# Sheet1.net
KiCad netlist of a schematic drawn in Altium Designer
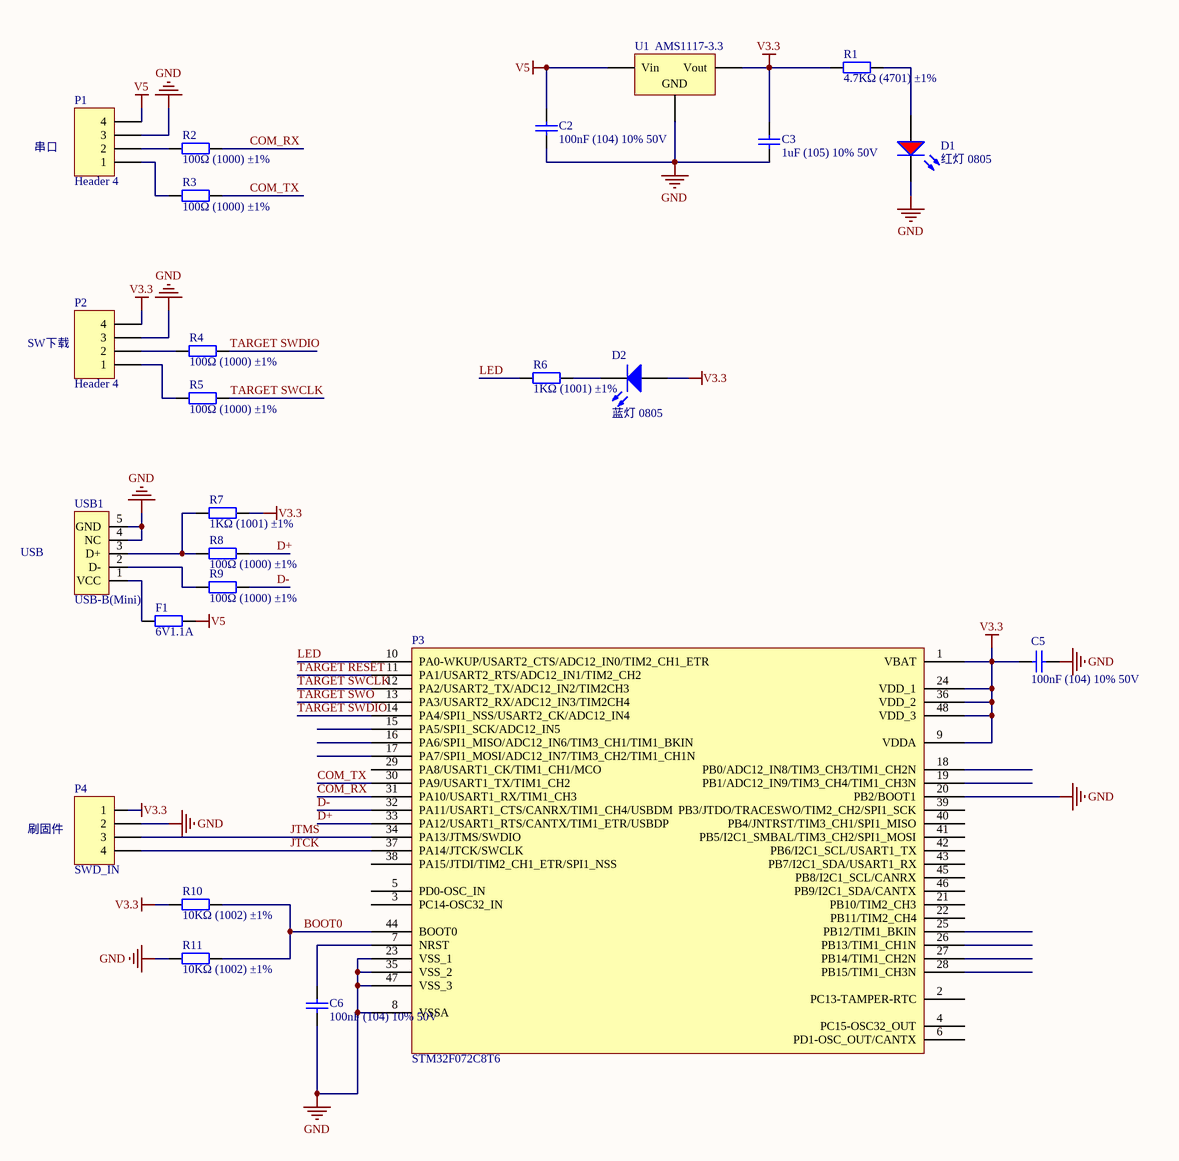
[diagram p0: Sheet1.SchDoc]

(export (version "E")
  (design (tool "Eeschema 10.0.6"))
  (components
    (comp (ref "C2")
      (value "100nF (104) 10% 50V")
      (footprint "0603_C")
      (description "贴片电容")
      (libsource (lib "Miscellaneous Devices LC") (part "0603 100nF (104) 10% 50V"))
    )
    (comp (ref "C3")
      (value "1uF (105) 10% 50V")
      (footprint "0603_C")
      (description "贴片电容")
      (libsource (lib "Miscellaneous Devices LC") (part "0603 1uF (105) 10% 50V"))
    )
    (comp (ref "C5")
      (value "100nF (104) 10% 50V")
      (footprint "0603_C")
      (description "贴片电容")
      (libsource (lib "Miscellaneous Devices LC") (part "0603 100nF (104) 10% 50V"))
    )
    (comp (ref "C6")
      (value "100nF (104) 10% 50V")
      (footprint "0603_C")
      (description "贴片电容")
      (libsource (lib "Miscellaneous Devices LC") (part "0603 100nF (104) 10% 50V"))
    )
    (comp (ref "D1")
      (value "红灯 0805")
      (footprint "0805_LED_S1")
      (description "发光二极管")
      (libsource (lib "Miscellaneous Devices LC") (part "0805 红灯"))
    )
    (comp (ref "D2")
      (value "蓝灯 0805")
      (footprint "0805_LED_S1")
      (description "发光二极管")
      (libsource (lib "Miscellaneous Devices LC") (part "0805 蓝灯"))
    )
    (comp (ref "F1")
      (value "6V1.1A")
      (footprint "0603_R")
      (description "贴片电阻")
      (libsource (lib "Miscellaneous Devices LC") (part "0603 0Ω (0R0) 1%"))
    )
    (comp (ref "P1")
      (value "Header 4")
      (footprint "IDE4_D")
      (description "Header, 4-Pin")
      (fields (field (name "PUBLISHER") "Altium Limited"))
      (libsource (lib "Miscellaneous Connectors") (part "Header 4"))
    )
    (comp (ref "P2")
      (value "Header 4")
      (footprint "IDE4_D")
      (description "Header, 4-Pin")
      (fields (field (name "PUBLISHER") "Altium Limited"))
      (libsource (lib "Miscellaneous Connectors") (part "Header 4"))
    )
    (comp (ref "P3")
      (value "STM32F072C8T6")
      (footprint "LQFP48_7X7X05P")
      (libsource (lib "MY_倒车雷达") (part "stm32f103v8t6"))
    )
    (comp (ref "P4")
      (value "SWD_IN")
      (footprint "HDR1X4")
      (description "Header, 4-Pin")
      (fields (field (name "PUBLISHER") "Altium Limited"))
      (libsource (lib "") (part "Header 4_1"))
    )
    (comp (ref "R1")
      (value "4.7KΩ (4701) ±1%")
      (footprint "0603_R")
      (description "贴片电阻")
      (libsource (lib "Miscellaneous Devices LC") (part "0603 4.7KΩ (4701) 1%"))
    )
    (comp (ref "R2")
      (value "100Ω (1000) ±1%")
      (footprint "0603_R")
      (description "贴片电阻")
      (libsource (lib "Miscellaneous Devices LC") (part "0603 100Ω (1000) 1%"))
    )
    (comp (ref "R3")
      (value "100Ω (1000) ±1%")
      (footprint "0603_R")
      (description "贴片电阻")
      (libsource (lib "Miscellaneous Devices LC") (part "0603 100Ω (1000) 1%"))
    )
    (comp (ref "R4")
      (value "100Ω (1000) ±1%")
      (footprint "0603_R")
      (description "贴片电阻")
      (libsource (lib "Miscellaneous Devices LC") (part "0603 100Ω (1000) 1%"))
    )
    (comp (ref "R5")
      (value "100Ω (1000) ±1%")
      (footprint "0603_R")
      (description "贴片电阻")
      (libsource (lib "Miscellaneous Devices LC") (part "0603 100Ω (1000) 1%"))
    )
    (comp (ref "R6")
      (value "1KΩ (1001) ±1%")
      (footprint "0603_R")
      (description "贴片电阻")
      (libsource (lib "Miscellaneous Devices LC") (part "0603 1KΩ (1001) 1%"))
    )
    (comp (ref "R7")
      (value "1KΩ (1001) ±1%")
      (footprint "0603_R")
      (description "贴片电阻")
      (libsource (lib "Miscellaneous Devices LC") (part "0603 1KΩ (1001) 1%"))
    )
    (comp (ref "R8")
      (value "100Ω (1000) ±1%")
      (footprint "0603_R")
      (description "贴片电阻")
      (libsource (lib "Miscellaneous Devices LC") (part "0603 100Ω (1000) 1%"))
    )
    (comp (ref "R9")
      (value "100Ω (1000) ±1%")
      (footprint "0603_R")
      (description "贴片电阻")
      (libsource (lib "Miscellaneous Devices LC") (part "0603 100Ω (1000) 1%"))
    )
    (comp (ref "R10")
      (value "10KΩ (1002) ±1%")
      (footprint "0603_R")
      (description "贴片电阻")
      (libsource (lib "Miscellaneous Devices LC") (part "0603 10KΩ (1002) 1%"))
    )
    (comp (ref "R11")
      (value "10KΩ (1002) ±1%")
      (footprint "0603_R")
      (description "贴片电阻")
      (libsource (lib "Miscellaneous Devices LC") (part "0603 10KΩ (1002) 1%"))
    )
    (comp (ref "U1")
      (value "AMS1117-3.3")
      (footprint "SOT-223")
      (description "低压差线性稳压(LDO)")
      (libsource (lib "Miscellaneous Devices LC") (part "SOT-223 AMS1117-3.3"))
    )
    (comp (ref "USB1")
      (value "USB-B(Mini)")
      (footprint "miniUSB")
      (libsource (lib "MY_倒车雷达") (part "miniUSB"))
    )
  )
  (nets
    (net (code "1") (name "/BOOT0") (class "Default")
      (node (ref "P3") (pin "44") (pinfunction "BOOT0_44") (pintype "passive"))
      (node (ref "R10") (pin "2") (pinfunction "2_2") (pintype "passive"))
      (node (ref "R11") (pin "2") (pinfunction "2_2") (pintype "passive"))
    )
    (net (code "2") (name "/COM_RX") (class "Default")
      (node (ref "P3") (pin "31") (pinfunction "PA10/USART1_RX/TIM1_CH3_31") (pintype "passive"))
      (node (ref "R2") (pin "2") (pinfunction "2_2") (pintype "passive"))
    )
    (net (code "3") (name "/COM_TX") (class "Default")
      (node (ref "P3") (pin "30") (pinfunction "PA9/USART1_TX/TIM1_CH2_30") (pintype "passive"))
      (node (ref "R3") (pin "2") (pinfunction "2_2") (pintype "passive"))
    )
    (net (code "4") (name "/D+") (class "Default")
      (node (ref "P3") (pin "33") (pinfunction "PA12/USART1_RTS/CANTX/TIM1_ETR/USBDP_33") (pintype "passive"))
      (node (ref "R8") (pin "2") (pinfunction "2_2") (pintype "passive"))
    )
    (net (code "5") (name "/D-") (class "Default")
      (node (ref "P3") (pin "32") (pinfunction "PA11/USART1_CTS/CANRX/TIM1_CH4/USBDM_32") (pintype "passive"))
      (node (ref "R9") (pin "2") (pinfunction "2_2") (pintype "passive"))
    )
    (net (code "6") (name "/JTCK") (class "Default")
      (node (ref "P3") (pin "37") (pinfunction "PA14/JTCK/SWCLK_37") (pintype "passive"))
      (node (ref "P4") (pin "4") (pinfunction "4_4") (pintype "passive"))
    )
    (net (code "7") (name "/JTMS") (class "Default")
      (node (ref "P3") (pin "34") (pinfunction "PA13/JTMS/SWDIO_34") (pintype "passive"))
      (node (ref "P4") (pin "3") (pinfunction "3_3") (pintype "passive"))
    )
    (net (code "8") (name "/LED") (class "Default")
      (node (ref "P3") (pin "10") (pinfunction "PA0-WKUP/USART2_CTS/ADC12_IN0/TIM2_CH1_ETR_10") (pintype "passive"))
      (node (ref "R6") (pin "1") (pinfunction "1_1") (pintype "passive"))
    )
    (net (code "9") (name "/TARGET RESET") (class "Default")
      (node (ref "P3") (pin "11") (pinfunction "PA1/USART2_RTS/ADC12_IN1/TIM2_CH2_11") (pintype "passive"))
    )
    (net (code "10") (name "/TARGET SWCLK") (class "Default")
      (node (ref "P3") (pin "12") (pinfunction "PA2/USART2_TX/ADC12_IN2/TIM2CH3_12") (pintype "passive"))
      (node (ref "R5") (pin "2") (pinfunction "2_2") (pintype "passive"))
    )
    (net (code "11") (name "/TARGET SWDIO") (class "Default")
      (node (ref "P3") (pin "14") (pinfunction "PA4/SPI1_NSS/USART2_CK/ADC12_IN4_14") (pintype "passive"))
      (node (ref "R4") (pin "2") (pinfunction "2_2") (pintype "passive"))
    )
    (net (code "12") (name "/TARGET SWO") (class "Default")
      (node (ref "P3") (pin "13") (pinfunction "PA3/USART2_RX/ADC12_IN3/TIM2CH4_13") (pintype "passive"))
    )
    (net (code "13") (name "GND") (class "Default")
      (node (ref "C2") (pin "2") (pinfunction "2_2") (pintype "passive"))
      (node (ref "C3") (pin "2") (pinfunction "2_2") (pintype "passive"))
      (node (ref "C5") (pin "2") (pinfunction "2_2") (pintype "passive"))
      (node (ref "C6") (pin "2") (pinfunction "2_2") (pintype "passive"))
      (node (ref "D1") (pin "K") (pinfunction "K_K") (pintype "passive"))
      (node (ref "P1") (pin "3") (pinfunction "3_3") (pintype "passive"))
      (node (ref "P2") (pin "3") (pinfunction "3_3") (pintype "passive"))
      (node (ref "P3") (pin "20") (pinfunction "PB2/BOOT1_20") (pintype "passive"))
      (node (ref "P3") (pin "23") (pinfunction "VSS_1_23") (pintype "passive"))
      (node (ref "P3") (pin "35") (pinfunction "VSS_2_35") (pintype "passive"))
      (node (ref "P3") (pin "47") (pinfunction "VSS_3_47") (pintype "passive"))
      (node (ref "P3") (pin "8") (pinfunction "VSSA_8") (pintype "passive"))
      (node (ref "P4") (pin "2") (pinfunction "2_2") (pintype "passive"))
      (node (ref "R11") (pin "1") (pinfunction "1_1") (pintype "passive"))
      (node (ref "U1") (pin "1") (pinfunction "GND_1") (pintype "passive"))
      (node (ref "USB1") (pin "4") (pinfunction "NC_4") (pintype "passive"))
      (node (ref "USB1") (pin "5") (pinfunction "GND_5") (pintype "passive"))
    )
    (net (code "14") (name "Net-(D1-PadA)") (class "Default")
      (node (ref "D1") (pin "A") (pinfunction "A_A") (pintype "passive"))
      (node (ref "R1") (pin "2") (pinfunction "2_2") (pintype "passive"))
    )
    (net (code "15") (name "Net-(D2-PadK)") (class "Default")
      (node (ref "D2") (pin "K") (pinfunction "K_K") (pintype "passive"))
      (node (ref "R6") (pin "2") (pinfunction "2_2") (pintype "passive"))
    )
    (net (code "16") (name "Net-(P1-Pad1)") (class "Default")
      (node (ref "P1") (pin "1") (pinfunction "1_1") (pintype "passive"))
      (node (ref "R3") (pin "1") (pinfunction "1_1") (pintype "passive"))
    )
    (net (code "17") (name "Net-(P1-Pad2)") (class "Default")
      (node (ref "P1") (pin "2") (pinfunction "2_2") (pintype "passive"))
      (node (ref "R2") (pin "1") (pinfunction "1_1") (pintype "passive"))
    )
    (net (code "18") (name "Net-(P2-Pad1)") (class "Default")
      (node (ref "P2") (pin "1") (pinfunction "1_1") (pintype "passive"))
      (node (ref "R5") (pin "1") (pinfunction "1_1") (pintype "passive"))
    )
    (net (code "19") (name "Net-(P2-Pad2)") (class "Default")
      (node (ref "P2") (pin "2") (pinfunction "2_2") (pintype "passive"))
      (node (ref "R4") (pin "1") (pinfunction "1_1") (pintype "passive"))
    )
    (net (code "20") (name "Net-(P3-NRST)") (class "Default")
      (node (ref "C6") (pin "1") (pinfunction "1_1") (pintype "passive"))
      (node (ref "P3") (pin "7") (pinfunction "NRST_7") (pintype "passive"))
    )
    (net (code "21") (name "Net-(USB1-D+)") (class "Default")
      (node (ref "R7") (pin "1") (pinfunction "1_1") (pintype "passive"))
      (node (ref "R8") (pin "1") (pinfunction "1_1") (pintype "passive"))
      (node (ref "USB1") (pin "3") (pinfunction "D+_3") (pintype "passive"))
    )
    (net (code "22") (name "Net-(USB1-D-)") (class "Default")
      (node (ref "R9") (pin "1") (pinfunction "1_1") (pintype "passive"))
      (node (ref "USB1") (pin "2") (pinfunction "D-_2") (pintype "passive"))
    )
    (net (code "23") (name "Net-(USB1-VCC)") (class "Default")
      (node (ref "F1") (pin "1") (pinfunction "1_1") (pintype "passive"))
      (node (ref "USB1") (pin "1") (pinfunction "VCC_1") (pintype "passive"))
    )
    (net (code "24") (name "V3.3") (class "Default")
      (node (ref "C3") (pin "1") (pinfunction "1_1") (pintype "passive"))
      (node (ref "C5") (pin "1") (pinfunction "1_1") (pintype "passive"))
      (node (ref "D2") (pin "A") (pinfunction "A_A") (pintype "passive"))
      (node (ref "P2") (pin "4") (pinfunction "4_4") (pintype "passive"))
      (node (ref "P3") (pin "1") (pinfunction "VBAT_1") (pintype "passive"))
      (node (ref "P3") (pin "24") (pinfunction "VDD_1_24") (pintype "passive"))
      (node (ref "P3") (pin "36") (pinfunction "VDD_2_36") (pintype "passive"))
      (node (ref "P3") (pin "48") (pinfunction "VDD_3_48") (pintype "passive"))
      (node (ref "P3") (pin "9") (pinfunction "VDDA_9") (pintype "passive"))
      (node (ref "P4") (pin "1") (pinfunction "1_1") (pintype "passive"))
      (node (ref "R1") (pin "1") (pinfunction "1_1") (pintype "passive"))
      (node (ref "R10") (pin "1") (pinfunction "1_1") (pintype "passive"))
      (node (ref "R7") (pin "2") (pinfunction "2_2") (pintype "passive"))
      (node (ref "U1") (pin "2") (pinfunction "Vout_2") (pintype "passive"))
    )
    (net (code "25") (name "V5") (class "Default")
      (node (ref "C2") (pin "1") (pinfunction "1_1") (pintype "passive"))
      (node (ref "F1") (pin "2") (pinfunction "2_2") (pintype "passive"))
      (node (ref "P1") (pin "4") (pinfunction "4_4") (pintype "passive"))
      (node (ref "U1") (pin "3") (pinfunction "Vin_3") (pintype "passive"))
    )
    (net (code "26") (name "unconnected-(P3-PA5{slash}SPI1_SCK{slash}ADC12_IN5-Pad15)") (class "Default")
      (node (ref "P3") (pin "15") (pinfunction "PA5/SPI1_SCK/ADC12_IN5_15") (pintype "passive"))
    )
    (net (code "27") (name "unconnected-(P3-PA6{slash}SPI1_MISO{slash}ADC12_IN6{slash}TIM3_CH1{slash}TIM1_BKIN-Pad16)") (class "Default")
      (node (ref "P3") (pin "16") (pinfunction "PA6/SPI1_MISO/ADC12_IN6/TIM3_CH1/TIM1_BKIN_16") (pintype "passive"))
    )
    (net (code "28") (name "unconnected-(P3-PA7{slash}SPI1_MOSI{slash}ADC12_IN7{slash}TIM3_CH2{slash}TIM1_CH1N-Pad17)") (class "Default")
      (node (ref "P3") (pin "17") (pinfunction "PA7/SPI1_MOSI/ADC12_IN7/TIM3_CH2/TIM1_CH1N_17") (pintype "passive"))
    )
    (net (code "29") (name "unconnected-(P3-PA8{slash}USART1_CK{slash}TIM1_CH1{slash}MCO-Pad29)") (class "Default")
      (node (ref "P3") (pin "29") (pinfunction "PA8/USART1_CK/TIM1_CH1/MCO_29") (pintype "passive"))
    )
    (net (code "30") (name "unconnected-(P3-PA15{slash}JTDI{slash}TIM2_CH1_ETR{slash}SPI1_NSS-Pad38)") (class "Default")
      (node (ref "P3") (pin "38") (pinfunction "PA15/JTDI/TIM2_CH1_ETR/SPI1_NSS_38") (pintype "passive"))
    )
    (net (code "31") (name "unconnected-(P3-PB0{slash}ADC12_IN8{slash}TIM3_CH3{slash}TIM1_CH2N-Pad18)") (class "Default")
      (node (ref "P3") (pin "18") (pinfunction "PB0/ADC12_IN8/TIM3_CH3/TIM1_CH2N_18") (pintype "passive"))
    )
    (net (code "32") (name "unconnected-(P3-PB1{slash}ADC12_IN9{slash}TIM3_CH4{slash}TIM1_CH3N-Pad19)") (class "Default")
      (node (ref "P3") (pin "19") (pinfunction "PB1/ADC12_IN9/TIM3_CH4/TIM1_CH3N_19") (pintype "passive"))
    )
    (net (code "33") (name "unconnected-(P3-PB3{slash}JTDO{slash}TRACESWO{slash}TIM2_CH2{slash}SPI1_SCK-Pad39)") (class "Default")
      (node (ref "P3") (pin "39") (pinfunction "PB3/JTDO/TRACESWO/TIM2_CH2/SPI1_SCK_39") (pintype "passive"))
    )
    (net (code "34") (name "unconnected-(P3-PB4{slash}JNTRST{slash}TIM3_CH1{slash}SPI1_MISO-Pad40)") (class "Default")
      (node (ref "P3") (pin "40") (pinfunction "PB4/JNTRST/TIM3_CH1/SPI1_MISO_40") (pintype "passive"))
    )
    (net (code "35") (name "unconnected-(P3-PB5{slash}I2C1_SMBAL{slash}TIM3_CH2{slash}SPI1_MOSI-Pad41)") (class "Default")
      (node (ref "P3") (pin "41") (pinfunction "PB5/I2C1_SMBAL/TIM3_CH2/SPI1_MOSI_41") (pintype "passive"))
    )
    (net (code "36") (name "unconnected-(P3-PB6{slash}I2C1_SCL{slash}USART1_TX-Pad42)") (class "Default")
      (node (ref "P3") (pin "42") (pinfunction "PB6/I2C1_SCL/USART1_TX_42") (pintype "passive"))
    )
    (net (code "37") (name "unconnected-(P3-PB7{slash}I2C1_SDA{slash}USART1_RX-Pad43)") (class "Default")
      (node (ref "P3") (pin "43") (pinfunction "PB7/I2C1_SDA/USART1_RX_43") (pintype "passive"))
    )
    (net (code "38") (name "unconnected-(P3-PB8{slash}I2C1_SCL{slash}CANRX-Pad45)") (class "Default")
      (node (ref "P3") (pin "45") (pinfunction "PB8/I2C1_SCL/CANRX_45") (pintype "passive"))
    )
    (net (code "39") (name "unconnected-(P3-PB9{slash}I2C1_SDA{slash}CANTX-Pad46)") (class "Default")
      (node (ref "P3") (pin "46") (pinfunction "PB9/I2C1_SDA/CANTX_46") (pintype "passive"))
    )
    (net (code "40") (name "unconnected-(P3-PB10{slash}TIM2_CH3-Pad21)") (class "Default")
      (node (ref "P3") (pin "21") (pinfunction "PB10/TIM2_CH3_21") (pintype "passive"))
    )
    (net (code "41") (name "unconnected-(P3-PB11{slash}TIM2_CH4-Pad22)") (class "Default")
      (node (ref "P3") (pin "22") (pinfunction "PB11/TIM2_CH4_22") (pintype "passive"))
    )
    (net (code "42") (name "unconnected-(P3-PB12{slash}TIM1_BKIN-Pad25)") (class "Default")
      (node (ref "P3") (pin "25") (pinfunction "PB12/TIM1_BKIN_25") (pintype "passive"))
    )
    (net (code "43") (name "unconnected-(P3-PB13{slash}TIM1_CH1N-Pad26)") (class "Default")
      (node (ref "P3") (pin "26") (pinfunction "PB13/TIM1_CH1N_26") (pintype "passive"))
    )
    (net (code "44") (name "unconnected-(P3-PB14{slash}TIM1_CH2N-Pad27)") (class "Default")
      (node (ref "P3") (pin "27") (pinfunction "PB14/TIM1_CH2N_27") (pintype "passive"))
    )
    (net (code "45") (name "unconnected-(P3-PB15{slash}TIM1_CH3N-Pad28)") (class "Default")
      (node (ref "P3") (pin "28") (pinfunction "PB15/TIM1_CH3N_28") (pintype "passive"))
    )
    (net (code "46") (name "unconnected-(P3-PC13-TAMPER-RTC-Pad2)") (class "Default")
      (node (ref "P3") (pin "2") (pinfunction "PC13-TAMPER-RTC_2") (pintype "passive"))
    )
    (net (code "47") (name "unconnected-(P3-PC14-OSC32_IN-Pad3)") (class "Default")
      (node (ref "P3") (pin "3") (pinfunction "PC14-OSC32_IN_3") (pintype "passive"))
    )
    (net (code "48") (name "unconnected-(P3-PC15-OSC32_OUT-Pad4)") (class "Default")
      (node (ref "P3") (pin "4") (pinfunction "PC15-OSC32_OUT_4") (pintype "passive"))
    )
    (net (code "49") (name "unconnected-(P3-PD0-OSC_IN-Pad5)") (class "Default")
      (node (ref "P3") (pin "5") (pinfunction "PD0-OSC_IN_5") (pintype "passive"))
    )
    (net (code "50") (name "unconnected-(P3-PD1-OSC_OUT{slash}CANTX-Pad6)") (class "Default")
      (node (ref "P3") (pin "6") (pinfunction "PD1-OSC_OUT/CANTX_6") (pintype "passive"))
    )
  )
)
